# GD_Tcontroller_Relay.net
KiCad netlist of a schematic drawn in Altium Designer
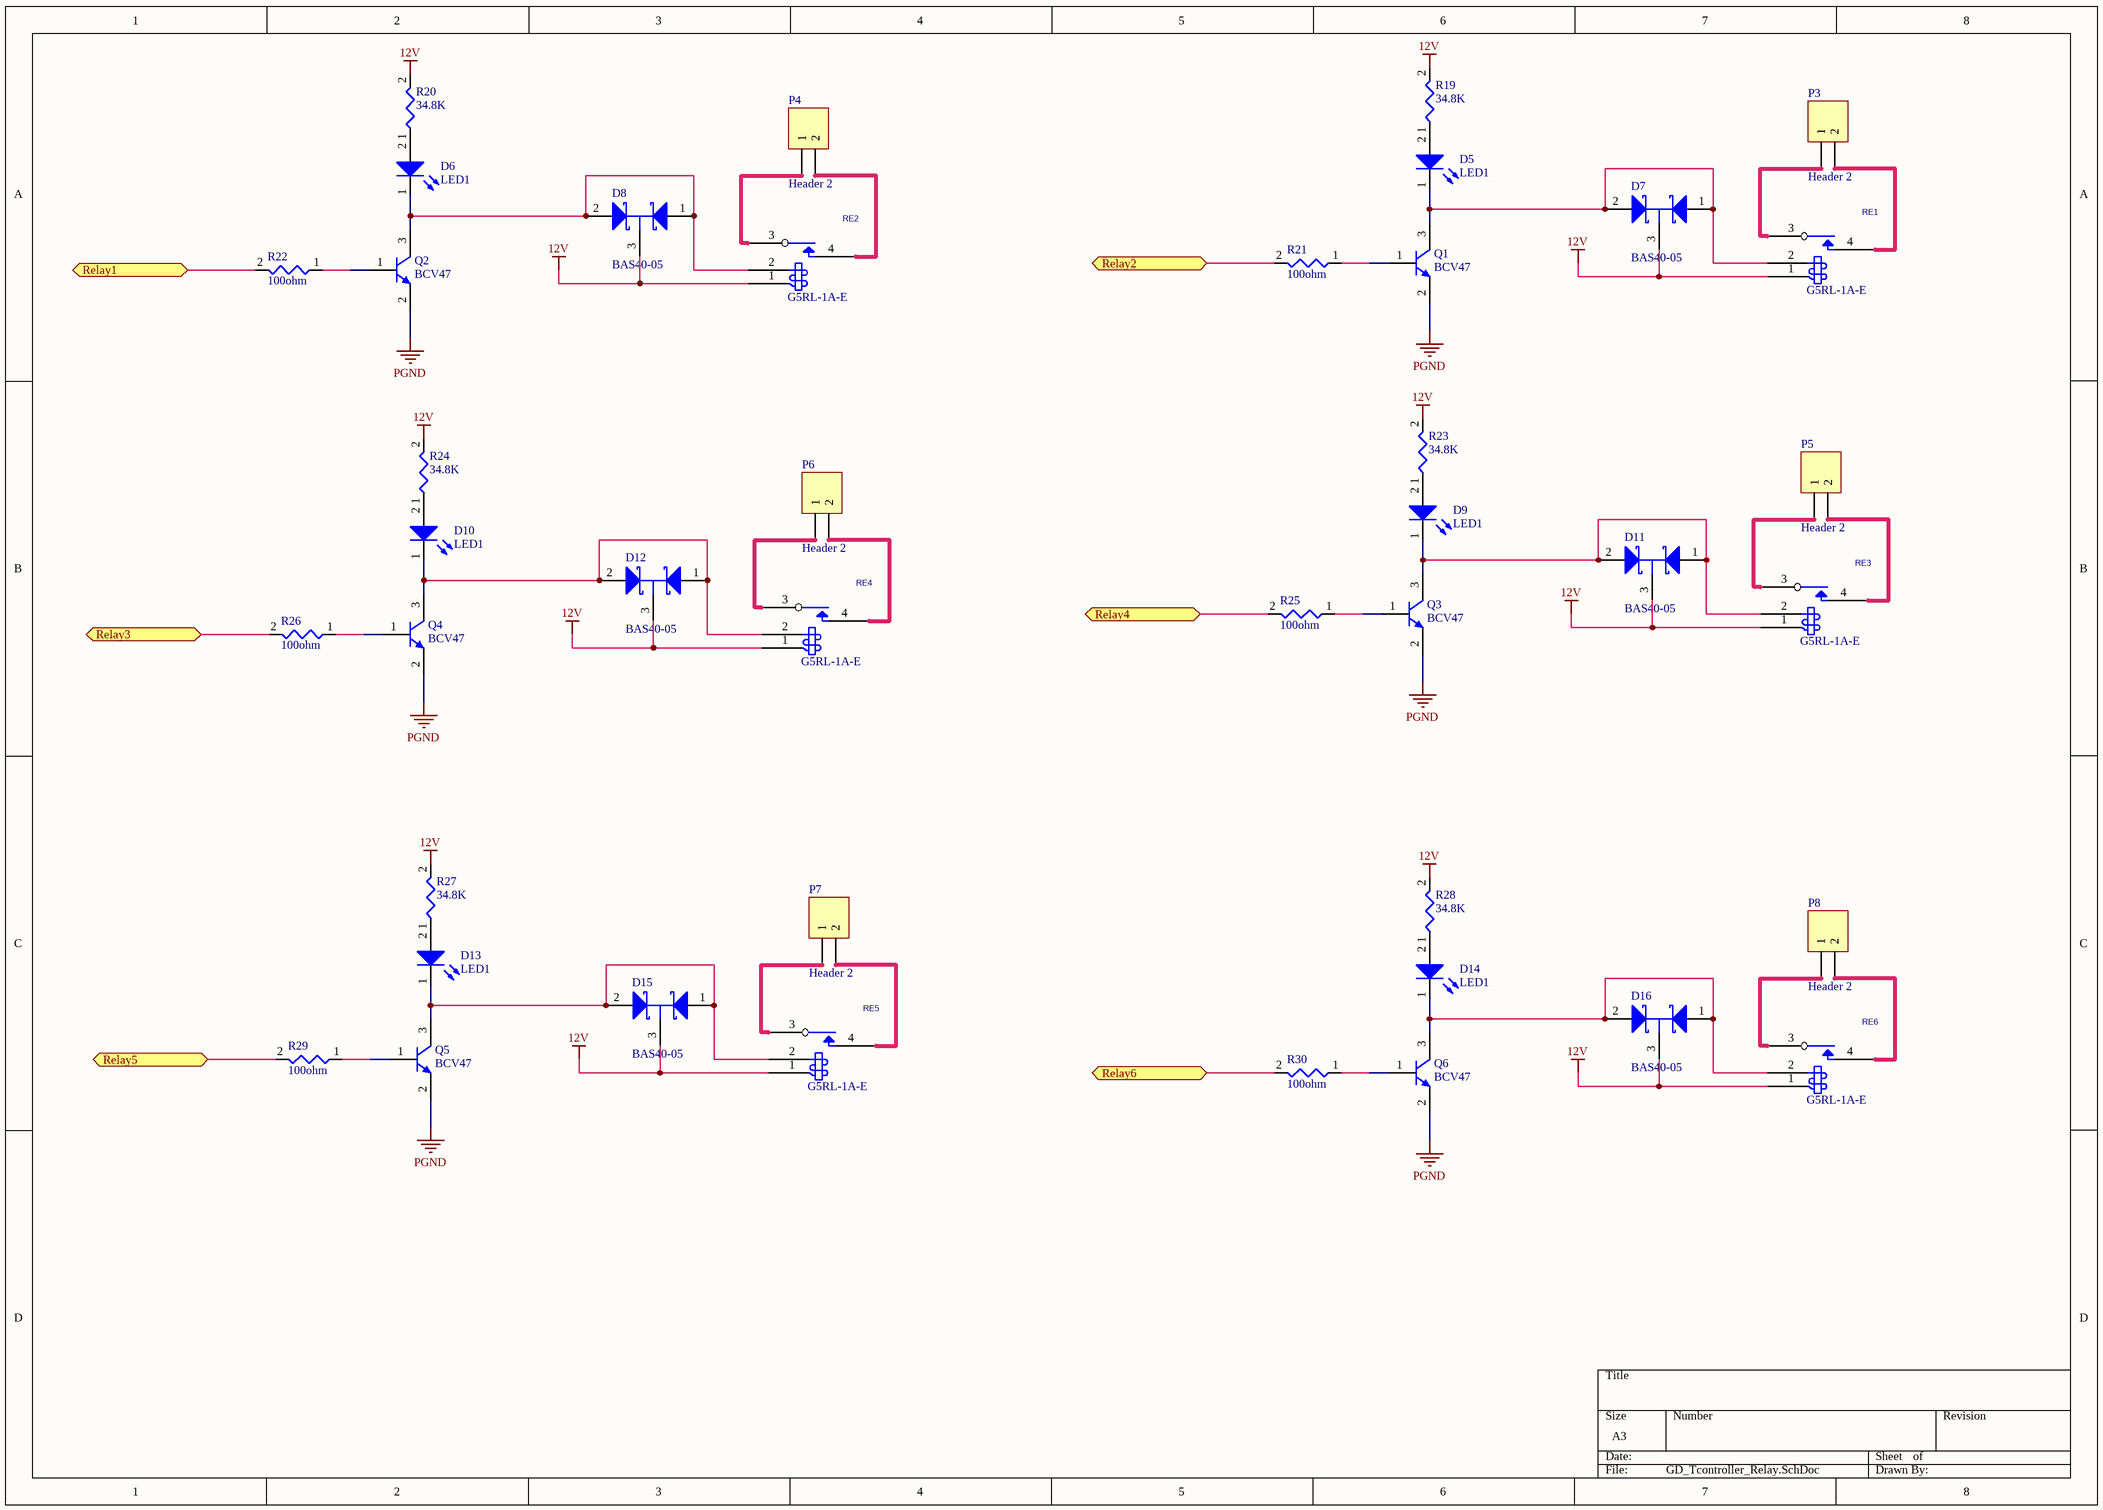
[diagram p0: GD_Tcontroller_Relay.SchDoc]

(export (version "E")
  (design (tool "Eeschema 10.0.6"))
  (components
    (comp (ref "D5")
      (value "LED1")
      (footprint "LED0603")
      (description "LED BLUE 1.6x0.8x0.3mm,SMD ROHS")
      (fields (field (name "MANUFACTURER") "OSRAM"))
      (libsource (lib "enlogic") (part "LED1"))
    )
    (comp (ref "D6")
      (value "LED1")
      (footprint "LED0603")
      (description "LED BLUE 1.6x0.8x0.3mm,SMD ROHS")
      (fields (field (name "MANUFACTURER") "OSRAM"))
      (libsource (lib "enlogic") (part "LED1"))
    )
    (comp (ref "D7")
      (value "BAS40-05")
      (footprint "SOT23-123")
      (description "DIODE Schottky Diode 40V 0.2A SOT-23 SMD ROHS")
      (fields (field (name "MANUFACTURER") "NXP"))
      (libsource (lib "enlogic") (part "BAS40-05"))
    )
    (comp (ref "D8")
      (value "BAS40-05")
      (footprint "SOT23-123")
      (description "DIODE Schottky Diode 40V 0.2A SOT-23 SMD ROHS")
      (fields (field (name "MANUFACTURER") "NXP"))
      (libsource (lib "enlogic") (part "BAS40-05"))
    )
    (comp (ref "D9")
      (value "LED1")
      (footprint "LED0603")
      (description "LED BLUE 1.6x0.8x0.3mm,SMD ROHS")
      (fields (field (name "MANUFACTURER") "OSRAM"))
      (libsource (lib "enlogic") (part "LED1"))
    )
    (comp (ref "D10")
      (value "LED1")
      (footprint "LED0603")
      (description "LED BLUE 1.6x0.8x0.3mm,SMD ROHS")
      (fields (field (name "MANUFACTURER") "OSRAM"))
      (libsource (lib "enlogic") (part "LED1"))
    )
    (comp (ref "D11")
      (value "BAS40-05")
      (footprint "SOT23-123")
      (description "DIODE Schottky Diode 40V 0.2A SOT-23 SMD ROHS")
      (fields (field (name "MANUFACTURER") "NXP"))
      (libsource (lib "enlogic") (part "BAS40-05"))
    )
    (comp (ref "D12")
      (value "BAS40-05")
      (footprint "SOT23-123")
      (description "DIODE Schottky Diode 40V 0.2A SOT-23 SMD ROHS")
      (fields (field (name "MANUFACTURER") "NXP"))
      (libsource (lib "enlogic") (part "BAS40-05"))
    )
    (comp (ref "D13")
      (value "LED1")
      (footprint "LED0603")
      (description "LED BLUE 1.6x0.8x0.3mm,SMD ROHS")
      (fields (field (name "MANUFACTURER") "OSRAM"))
      (libsource (lib "enlogic") (part "LED1"))
    )
    (comp (ref "D14")
      (value "LED1")
      (footprint "LED0603")
      (description "LED BLUE 1.6x0.8x0.3mm,SMD ROHS")
      (fields (field (name "MANUFACTURER") "OSRAM"))
      (libsource (lib "enlogic") (part "LED1"))
    )
    (comp (ref "D15")
      (value "BAS40-05")
      (footprint "SOT23-123")
      (description "DIODE Schottky Diode 40V 0.2A SOT-23 SMD ROHS")
      (fields (field (name "MANUFACTURER") "NXP"))
      (libsource (lib "enlogic") (part "BAS40-05"))
    )
    (comp (ref "D16")
      (value "BAS40-05")
      (footprint "SOT23-123")
      (description "DIODE Schottky Diode 40V 0.2A SOT-23 SMD ROHS")
      (fields (field (name "MANUFACTURER") "NXP"))
      (libsource (lib "enlogic") (part "BAS40-05"))
    )
    (comp (ref "P3")
      (value "Header 2")
      (footprint "KF7.62-2P")
      (description "Header, 2-Pin")
      (fields (field (name "PUBLISHER") "Altium Limited"))
      (libsource (lib "Miscellaneous Connectors") (part "Header 2"))
    )
    (comp (ref "P4")
      (value "Header 2")
      (footprint "KF7.62-2P")
      (description "Header, 2-Pin")
      (fields (field (name "PUBLISHER") "Altium Limited"))
      (libsource (lib "Miscellaneous Connectors") (part "Header 2"))
    )
    (comp (ref "P5")
      (value "Header 2")
      (footprint "KF7.62-2P")
      (description "Header, 2-Pin")
      (fields (field (name "PUBLISHER") "Altium Limited"))
      (libsource (lib "Miscellaneous Connectors") (part "Header 2"))
    )
    (comp (ref "P6")
      (value "Header 2")
      (footprint "KF7.62-2P")
      (description "Header, 2-Pin")
      (fields (field (name "PUBLISHER") "Altium Limited"))
      (libsource (lib "Miscellaneous Connectors") (part "Header 2"))
    )
    (comp (ref "P7")
      (value "Header 2")
      (footprint "KF7.62-2P")
      (description "Header, 2-Pin")
      (fields (field (name "PUBLISHER") "Altium Limited"))
      (libsource (lib "Miscellaneous Connectors") (part "Header 2"))
    )
    (comp (ref "P8")
      (value "Header 2")
      (footprint "KF7.62-2P")
      (description "Header, 2-Pin")
      (fields (field (name "PUBLISHER") "Altium Limited"))
      (libsource (lib "Miscellaneous Connectors") (part "Header 2"))
    )
    (comp (ref "Q1")
      (value "BCV47")
      (footprint "INF-SOT23_L")
      (description "NPN Silicon Darlington Transistor, 60 V VCEO, 500 mA IC, SOT23, Reel, Green")
      (fields (field (name "MANUFACTURER") "Infineon"))
      (libsource (lib "Altium Content Vault") (part "CMP-1196-00014-1"))
    )
    (comp (ref "Q2")
      (value "BCV47")
      (footprint "INF-SOT23_L")
      (description "NPN Silicon Darlington Transistor, 60 V VCEO, 500 mA IC, SOT23, Reel, Green")
      (fields (field (name "MANUFACTURER") "Infineon"))
      (libsource (lib "Altium Content Vault") (part "CMP-1196-00014-1"))
    )
    (comp (ref "Q3")
      (value "BCV47")
      (footprint "INF-SOT23_L")
      (description "NPN Silicon Darlington Transistor, 60 V VCEO, 500 mA IC, SOT23, Reel, Green")
      (fields (field (name "MANUFACTURER") "Infineon"))
      (libsource (lib "Altium Content Vault") (part "CMP-1196-00014-1"))
    )
    (comp (ref "Q4")
      (value "BCV47")
      (footprint "INF-SOT23_L")
      (description "NPN Silicon Darlington Transistor, 60 V VCEO, 500 mA IC, SOT23, Reel, Green")
      (fields (field (name "MANUFACTURER") "Infineon"))
      (libsource (lib "Altium Content Vault") (part "CMP-1196-00014-1"))
    )
    (comp (ref "Q5")
      (value "BCV47")
      (footprint "INF-SOT23_L")
      (description "NPN Silicon Darlington Transistor, 60 V VCEO, 500 mA IC, SOT23, Reel, Green")
      (fields (field (name "MANUFACTURER") "Infineon"))
      (libsource (lib "Altium Content Vault") (part "CMP-1196-00014-1"))
    )
    (comp (ref "Q6")
      (value "BCV47")
      (footprint "INF-SOT23_L")
      (description "NPN Silicon Darlington Transistor, 60 V VCEO, 500 mA IC, SOT23, Reel, Green")
      (fields (field (name "MANUFACTURER") "Infineon"))
      (libsource (lib "Altium Content Vault") (part "CMP-1196-00014-1"))
    )
    (comp (ref "R19")
      (value "34.8K")
      (footprint "R0805")
      (description "RES THICK_FILM SMD 34.8K 1% 1/8W ROHS 0805")
      (fields (field (name "MANUFACTURER") "YAGEO") (field (name "Comment") "RES"))
      (libsource (lib "enlogic") (part "RES"))
    )
    (comp (ref "R20")
      (value "34.8K")
      (footprint "R0805")
      (description "RES THICK_FILM SMD 34.8K 1% 1/8W ROHS 0805")
      (fields (field (name "MANUFACTURER") "YAGEO") (field (name "Comment") "RES"))
      (libsource (lib "enlogic") (part "RES"))
    )
    (comp (ref "R21")
      (value "100ohm")
      (footprint "R0805")
      (description "RES THICK_FILM SMD 100 OHM 5% 1/8W ROHS 0805")
      (fields (field (name "MANUFACTURER") "YAGEO") (field (name "Comment") "RES"))
      (libsource (lib "enlogic") (part "RES"))
    )
    (comp (ref "R22")
      (value "100ohm")
      (footprint "R0805")
      (description "RES THICK_FILM SMD 100 OHM 5% 1/8W ROHS 0805")
      (fields (field (name "MANUFACTURER") "YAGEO") (field (name "Comment") "RES"))
      (libsource (lib "enlogic") (part "RES"))
    )
    (comp (ref "R23")
      (value "34.8K")
      (footprint "R0805")
      (description "RES THICK_FILM SMD 34.8K 1% 1/8W ROHS 0805")
      (fields (field (name "MANUFACTURER") "YAGEO") (field (name "Comment") "RES"))
      (libsource (lib "enlogic") (part "RES"))
    )
    (comp (ref "R24")
      (value "34.8K")
      (footprint "R0805")
      (description "RES THICK_FILM SMD 34.8K 1% 1/8W ROHS 0805")
      (fields (field (name "MANUFACTURER") "YAGEO") (field (name "Comment") "RES"))
      (libsource (lib "enlogic") (part "RES"))
    )
    (comp (ref "R25")
      (value "100ohm")
      (footprint "R0805")
      (description "RES THICK_FILM SMD 100 OHM 5% 1/8W ROHS 0805")
      (fields (field (name "MANUFACTURER") "YAGEO") (field (name "Comment") "RES"))
      (libsource (lib "enlogic") (part "RES"))
    )
    (comp (ref "R26")
      (value "100ohm")
      (footprint "R0805")
      (description "RES THICK_FILM SMD 100 OHM 5% 1/8W ROHS 0805")
      (fields (field (name "MANUFACTURER") "YAGEO") (field (name "Comment") "RES"))
      (libsource (lib "enlogic") (part "RES"))
    )
    (comp (ref "R27")
      (value "34.8K")
      (footprint "R0805")
      (description "RES THICK_FILM SMD 34.8K 1% 1/8W ROHS 0805")
      (fields (field (name "MANUFACTURER") "YAGEO") (field (name "Comment") "RES"))
      (libsource (lib "enlogic") (part "RES"))
    )
    (comp (ref "R28")
      (value "34.8K")
      (footprint "R0805")
      (description "RES THICK_FILM SMD 34.8K 1% 1/8W ROHS 0805")
      (fields (field (name "MANUFACTURER") "YAGEO") (field (name "Comment") "RES"))
      (libsource (lib "enlogic") (part "RES"))
    )
    (comp (ref "R29")
      (value "100ohm")
      (footprint "R0805")
      (description "RES THICK_FILM SMD 100 OHM 5% 1/8W ROHS 0805")
      (fields (field (name "MANUFACTURER") "YAGEO") (field (name "Comment") "RES"))
      (libsource (lib "enlogic") (part "RES"))
    )
    (comp (ref "R30")
      (value "100ohm")
      (footprint "R0805")
      (description "RES THICK_FILM SMD 100 OHM 5% 1/8W ROHS 0805")
      (fields (field (name "MANUFACTURER") "YAGEO") (field (name "Comment") "RES"))
      (libsource (lib "enlogic") (part "RES"))
    )
    (comp (ref "RE1")
      (value "RELAY SP")
      (footprint "G5RL-1A-E")
      (description "Relay,12VDC,16A,250VAC")
      (fields (field (name "MANUFACTURER") "OMRON") (field (name "MANUFACTURER P/N") "G5RL-1A-E"))
      (libsource (lib "enlogic") (part "RELAY SP"))
    )
    (comp (ref "RE2")
      (value "RELAY SP")
      (footprint "G5RL-1A-E")
      (description "Relay,12VDC,16A,250VAC")
      (fields (field (name "MANUFACTURER") "OMRON") (field (name "MANUFACTURER P/N") "G5RL-1A-E"))
      (libsource (lib "enlogic") (part "RELAY SP"))
    )
    (comp (ref "RE3")
      (value "RELAY SP")
      (footprint "G5RL-1A-E")
      (description "Relay,12VDC,16A,250VAC")
      (fields (field (name "MANUFACTURER") "OMRON") (field (name "MANUFACTURER P/N") "G5RL-1A-E"))
      (libsource (lib "enlogic") (part "RELAY SP"))
    )
    (comp (ref "RE4")
      (value "RELAY SP")
      (footprint "G5RL-1A-E")
      (description "Relay,12VDC,16A,250VAC")
      (fields (field (name "MANUFACTURER") "OMRON") (field (name "MANUFACTURER P/N") "G5RL-1A-E"))
      (libsource (lib "enlogic") (part "RELAY SP"))
    )
    (comp (ref "RE5")
      (value "RELAY SP")
      (footprint "G5RL-1A-E")
      (description "Relay,12VDC,16A,250VAC")
      (fields (field (name "MANUFACTURER") "OMRON") (field (name "MANUFACTURER P/N") "G5RL-1A-E"))
      (libsource (lib "enlogic") (part "RELAY SP"))
    )
    (comp (ref "RE6")
      (value "RELAY SP")
      (footprint "G5RL-1A-E")
      (description "Relay,12VDC,16A,250VAC")
      (fields (field (name "MANUFACTURER") "OMRON") (field (name "MANUFACTURER P/N") "G5RL-1A-E"))
      (libsource (lib "enlogic") (part "RELAY SP"))
    )
  )
  (nets
    (net (code "1") (name "/Relay1") (class "Default")
      (node (ref "R22") (pin "2") (pinfunction "2_2") (pintype "passive"))
    )
    (net (code "2") (name "/Relay2") (class "Default")
      (node (ref "R21") (pin "2") (pinfunction "2_2") (pintype "passive"))
    )
    (net (code "3") (name "/Relay3") (class "Default")
      (node (ref "R26") (pin "2") (pinfunction "2_2") (pintype "passive"))
    )
    (net (code "4") (name "/Relay4") (class "Default")
      (node (ref "R25") (pin "2") (pinfunction "2_2") (pintype "passive"))
    )
    (net (code "5") (name "/Relay5") (class "Default")
      (node (ref "R29") (pin "2") (pinfunction "2_2") (pintype "passive"))
    )
    (net (code "6") (name "/Relay6") (class "Default")
      (node (ref "R30") (pin "2") (pinfunction "2_2") (pintype "passive"))
    )
    (net (code "7") (name "12V") (class "Default")
      (node (ref "D11") (pin "3") (pinfunction "C_3") (pintype "passive"))
      (node (ref "D12") (pin "3") (pinfunction "C_3") (pintype "passive"))
      (node (ref "D15") (pin "3") (pinfunction "C_3") (pintype "passive"))
      (node (ref "D16") (pin "3") (pinfunction "C_3") (pintype "passive"))
      (node (ref "D7") (pin "3") (pinfunction "C_3") (pintype "passive"))
      (node (ref "D8") (pin "3") (pinfunction "C_3") (pintype "passive"))
      (node (ref "R19") (pin "2") (pinfunction "2_2") (pintype "passive"))
      (node (ref "R20") (pin "2") (pinfunction "2_2") (pintype "passive"))
      (node (ref "R23") (pin "2") (pinfunction "2_2") (pintype "passive"))
      (node (ref "R24") (pin "2") (pinfunction "2_2") (pintype "passive"))
      (node (ref "R27") (pin "2") (pinfunction "2_2") (pintype "passive"))
      (node (ref "R28") (pin "2") (pinfunction "2_2") (pintype "passive"))
      (node (ref "RE1") (pin "1") (pinfunction "COIL_1") (pintype "passive"))
      (node (ref "RE2") (pin "1") (pinfunction "COIL_1") (pintype "passive"))
      (node (ref "RE3") (pin "1") (pinfunction "COIL_1") (pintype "passive"))
      (node (ref "RE4") (pin "1") (pinfunction "COIL_1") (pintype "passive"))
      (node (ref "RE5") (pin "1") (pinfunction "COIL_1") (pintype "passive"))
      (node (ref "RE6") (pin "1") (pinfunction "COIL_1") (pintype "passive"))
    )
    (net (code "8") (name "Net-(D5-Pad2)") (class "Default")
      (node (ref "D5") (pin "2") (pinfunction "2_2") (pintype "passive"))
      (node (ref "R19") (pin "1") (pinfunction "1_1") (pintype "passive"))
    )
    (net (code "9") (name "Net-(D6-Pad2)") (class "Default")
      (node (ref "D6") (pin "2") (pinfunction "2_2") (pintype "passive"))
      (node (ref "R20") (pin "1") (pinfunction "1_1") (pintype "passive"))
    )
    (net (code "10") (name "Net-(D7-A)") (class "Default")
      (node (ref "D5") (pin "1") (pinfunction "1_1") (pintype "passive"))
      (node (ref "D7") (pin "1") (pinfunction "A_1") (pintype "passive"))
      (node (ref "D7") (pin "2") (pinfunction "K_2") (pintype "passive"))
      (node (ref "Q1") (pin "3") (pinfunction "C_3") (pintype "passive"))
      (node (ref "RE1") (pin "2") (pinfunction "COIL_2") (pintype "passive"))
    )
    (net (code "11") (name "Net-(D8-A)") (class "Default")
      (node (ref "D6") (pin "1") (pinfunction "1_1") (pintype "passive"))
      (node (ref "D8") (pin "1") (pinfunction "A_1") (pintype "passive"))
      (node (ref "D8") (pin "2") (pinfunction "K_2") (pintype "passive"))
      (node (ref "Q2") (pin "3") (pinfunction "C_3") (pintype "passive"))
      (node (ref "RE2") (pin "2") (pinfunction "COIL_2") (pintype "passive"))
    )
    (net (code "12") (name "Net-(D9-Pad2)") (class "Default")
      (node (ref "D9") (pin "2") (pinfunction "2_2") (pintype "passive"))
      (node (ref "R23") (pin "1") (pinfunction "1_1") (pintype "passive"))
    )
    (net (code "13") (name "Net-(D10-Pad2)") (class "Default")
      (node (ref "D10") (pin "2") (pinfunction "2_2") (pintype "passive"))
      (node (ref "R24") (pin "1") (pinfunction "1_1") (pintype "passive"))
    )
    (net (code "14") (name "Net-(D11-A)") (class "Default")
      (node (ref "D11") (pin "1") (pinfunction "A_1") (pintype "passive"))
      (node (ref "D11") (pin "2") (pinfunction "K_2") (pintype "passive"))
      (node (ref "D9") (pin "1") (pinfunction "1_1") (pintype "passive"))
      (node (ref "Q3") (pin "3") (pinfunction "C_3") (pintype "passive"))
      (node (ref "RE3") (pin "2") (pinfunction "COIL_2") (pintype "passive"))
    )
    (net (code "15") (name "Net-(D12-A)") (class "Default")
      (node (ref "D10") (pin "1") (pinfunction "1_1") (pintype "passive"))
      (node (ref "D12") (pin "1") (pinfunction "A_1") (pintype "passive"))
      (node (ref "D12") (pin "2") (pinfunction "K_2") (pintype "passive"))
      (node (ref "Q4") (pin "3") (pinfunction "C_3") (pintype "passive"))
      (node (ref "RE4") (pin "2") (pinfunction "COIL_2") (pintype "passive"))
    )
    (net (code "16") (name "Net-(D13-Pad2)") (class "Default")
      (node (ref "D13") (pin "2") (pinfunction "2_2") (pintype "passive"))
      (node (ref "R27") (pin "1") (pinfunction "1_1") (pintype "passive"))
    )
    (net (code "17") (name "Net-(D14-Pad2)") (class "Default")
      (node (ref "D14") (pin "2") (pinfunction "2_2") (pintype "passive"))
      (node (ref "R28") (pin "1") (pinfunction "1_1") (pintype "passive"))
    )
    (net (code "18") (name "Net-(D15-A)") (class "Default")
      (node (ref "D13") (pin "1") (pinfunction "1_1") (pintype "passive"))
      (node (ref "D15") (pin "1") (pinfunction "A_1") (pintype "passive"))
      (node (ref "D15") (pin "2") (pinfunction "K_2") (pintype "passive"))
      (node (ref "Q5") (pin "3") (pinfunction "C_3") (pintype "passive"))
      (node (ref "RE5") (pin "2") (pinfunction "COIL_2") (pintype "passive"))
    )
    (net (code "19") (name "Net-(D16-A)") (class "Default")
      (node (ref "D14") (pin "1") (pinfunction "1_1") (pintype "passive"))
      (node (ref "D16") (pin "1") (pinfunction "A_1") (pintype "passive"))
      (node (ref "D16") (pin "2") (pinfunction "K_2") (pintype "passive"))
      (node (ref "Q6") (pin "3") (pinfunction "C_3") (pintype "passive"))
      (node (ref "RE6") (pin "2") (pinfunction "COIL_2") (pintype "passive"))
    )
    (net (code "20") (name "Net-(Q1-B)") (class "Default")
      (node (ref "Q1") (pin "1") (pinfunction "B_1") (pintype "passive"))
      (node (ref "R21") (pin "1") (pinfunction "1_1") (pintype "passive"))
    )
    (net (code "21") (name "Net-(Q2-B)") (class "Default")
      (node (ref "Q2") (pin "1") (pinfunction "B_1") (pintype "passive"))
      (node (ref "R22") (pin "1") (pinfunction "1_1") (pintype "passive"))
    )
    (net (code "22") (name "Net-(Q3-B)") (class "Default")
      (node (ref "Q3") (pin "1") (pinfunction "B_1") (pintype "passive"))
      (node (ref "R25") (pin "1") (pinfunction "1_1") (pintype "passive"))
    )
    (net (code "23") (name "Net-(Q4-B)") (class "Default")
      (node (ref "Q4") (pin "1") (pinfunction "B_1") (pintype "passive"))
      (node (ref "R26") (pin "1") (pinfunction "1_1") (pintype "passive"))
    )
    (net (code "24") (name "Net-(Q5-B)") (class "Default")
      (node (ref "Q5") (pin "1") (pinfunction "B_1") (pintype "passive"))
      (node (ref "R29") (pin "1") (pinfunction "1_1") (pintype "passive"))
    )
    (net (code "25") (name "Net-(Q6-B)") (class "Default")
      (node (ref "Q6") (pin "1") (pinfunction "B_1") (pintype "passive"))
      (node (ref "R30") (pin "1") (pinfunction "1_1") (pintype "passive"))
    )
    (net (code "26") (name "Net-(RE1-COMMON)") (class "Default")
      (node (ref "P3") (pin "1") (pinfunction "1_1") (pintype "passive"))
      (node (ref "RE1") (pin "3") (pinfunction "COMMON_3") (pintype "passive"))
    )
    (net (code "27") (name "Net-(RE1-NO)") (class "Default")
      (node (ref "P3") (pin "2") (pinfunction "2_2") (pintype "passive"))
      (node (ref "RE1") (pin "4") (pinfunction "NO_4") (pintype "passive"))
    )
    (net (code "28") (name "Net-(RE2-COMMON)") (class "Default")
      (node (ref "P4") (pin "1") (pinfunction "1_1") (pintype "passive"))
      (node (ref "RE2") (pin "3") (pinfunction "COMMON_3") (pintype "passive"))
    )
    (net (code "29") (name "Net-(RE2-NO)") (class "Default")
      (node (ref "P4") (pin "2") (pinfunction "2_2") (pintype "passive"))
      (node (ref "RE2") (pin "4") (pinfunction "NO_4") (pintype "passive"))
    )
    (net (code "30") (name "Net-(RE3-COMMON)") (class "Default")
      (node (ref "P5") (pin "1") (pinfunction "1_1") (pintype "passive"))
      (node (ref "RE3") (pin "3") (pinfunction "COMMON_3") (pintype "passive"))
    )
    (net (code "31") (name "Net-(RE3-NO)") (class "Default")
      (node (ref "P5") (pin "2") (pinfunction "2_2") (pintype "passive"))
      (node (ref "RE3") (pin "4") (pinfunction "NO_4") (pintype "passive"))
    )
    (net (code "32") (name "Net-(RE4-COMMON)") (class "Default")
      (node (ref "P6") (pin "1") (pinfunction "1_1") (pintype "passive"))
      (node (ref "RE4") (pin "3") (pinfunction "COMMON_3") (pintype "passive"))
    )
    (net (code "33") (name "Net-(RE4-NO)") (class "Default")
      (node (ref "P6") (pin "2") (pinfunction "2_2") (pintype "passive"))
      (node (ref "RE4") (pin "4") (pinfunction "NO_4") (pintype "passive"))
    )
    (net (code "34") (name "Net-(RE5-COMMON)") (class "Default")
      (node (ref "P7") (pin "1") (pinfunction "1_1") (pintype "passive"))
      (node (ref "RE5") (pin "3") (pinfunction "COMMON_3") (pintype "passive"))
    )
    (net (code "35") (name "Net-(RE5-NO)") (class "Default")
      (node (ref "P7") (pin "2") (pinfunction "2_2") (pintype "passive"))
      (node (ref "RE5") (pin "4") (pinfunction "NO_4") (pintype "passive"))
    )
    (net (code "36") (name "Net-(RE6-COMMON)") (class "Default")
      (node (ref "P8") (pin "1") (pinfunction "1_1") (pintype "passive"))
      (node (ref "RE6") (pin "3") (pinfunction "COMMON_3") (pintype "passive"))
    )
    (net (code "37") (name "Net-(RE6-NO)") (class "Default")
      (node (ref "P8") (pin "2") (pinfunction "2_2") (pintype "passive"))
      (node (ref "RE6") (pin "4") (pinfunction "NO_4") (pintype "passive"))
    )
    (net (code "38") (name "PGND") (class "Default")
      (node (ref "Q1") (pin "2") (pinfunction "E_2") (pintype "passive"))
      (node (ref "Q2") (pin "2") (pinfunction "E_2") (pintype "passive"))
      (node (ref "Q3") (pin "2") (pinfunction "E_2") (pintype "passive"))
      (node (ref "Q4") (pin "2") (pinfunction "E_2") (pintype "passive"))
      (node (ref "Q5") (pin "2") (pinfunction "E_2") (pintype "passive"))
      (node (ref "Q6") (pin "2") (pinfunction "E_2") (pintype "passive"))
    )
  )
)
